# Sheet1.net
KiCad netlist of a schematic drawn in Altium Designer
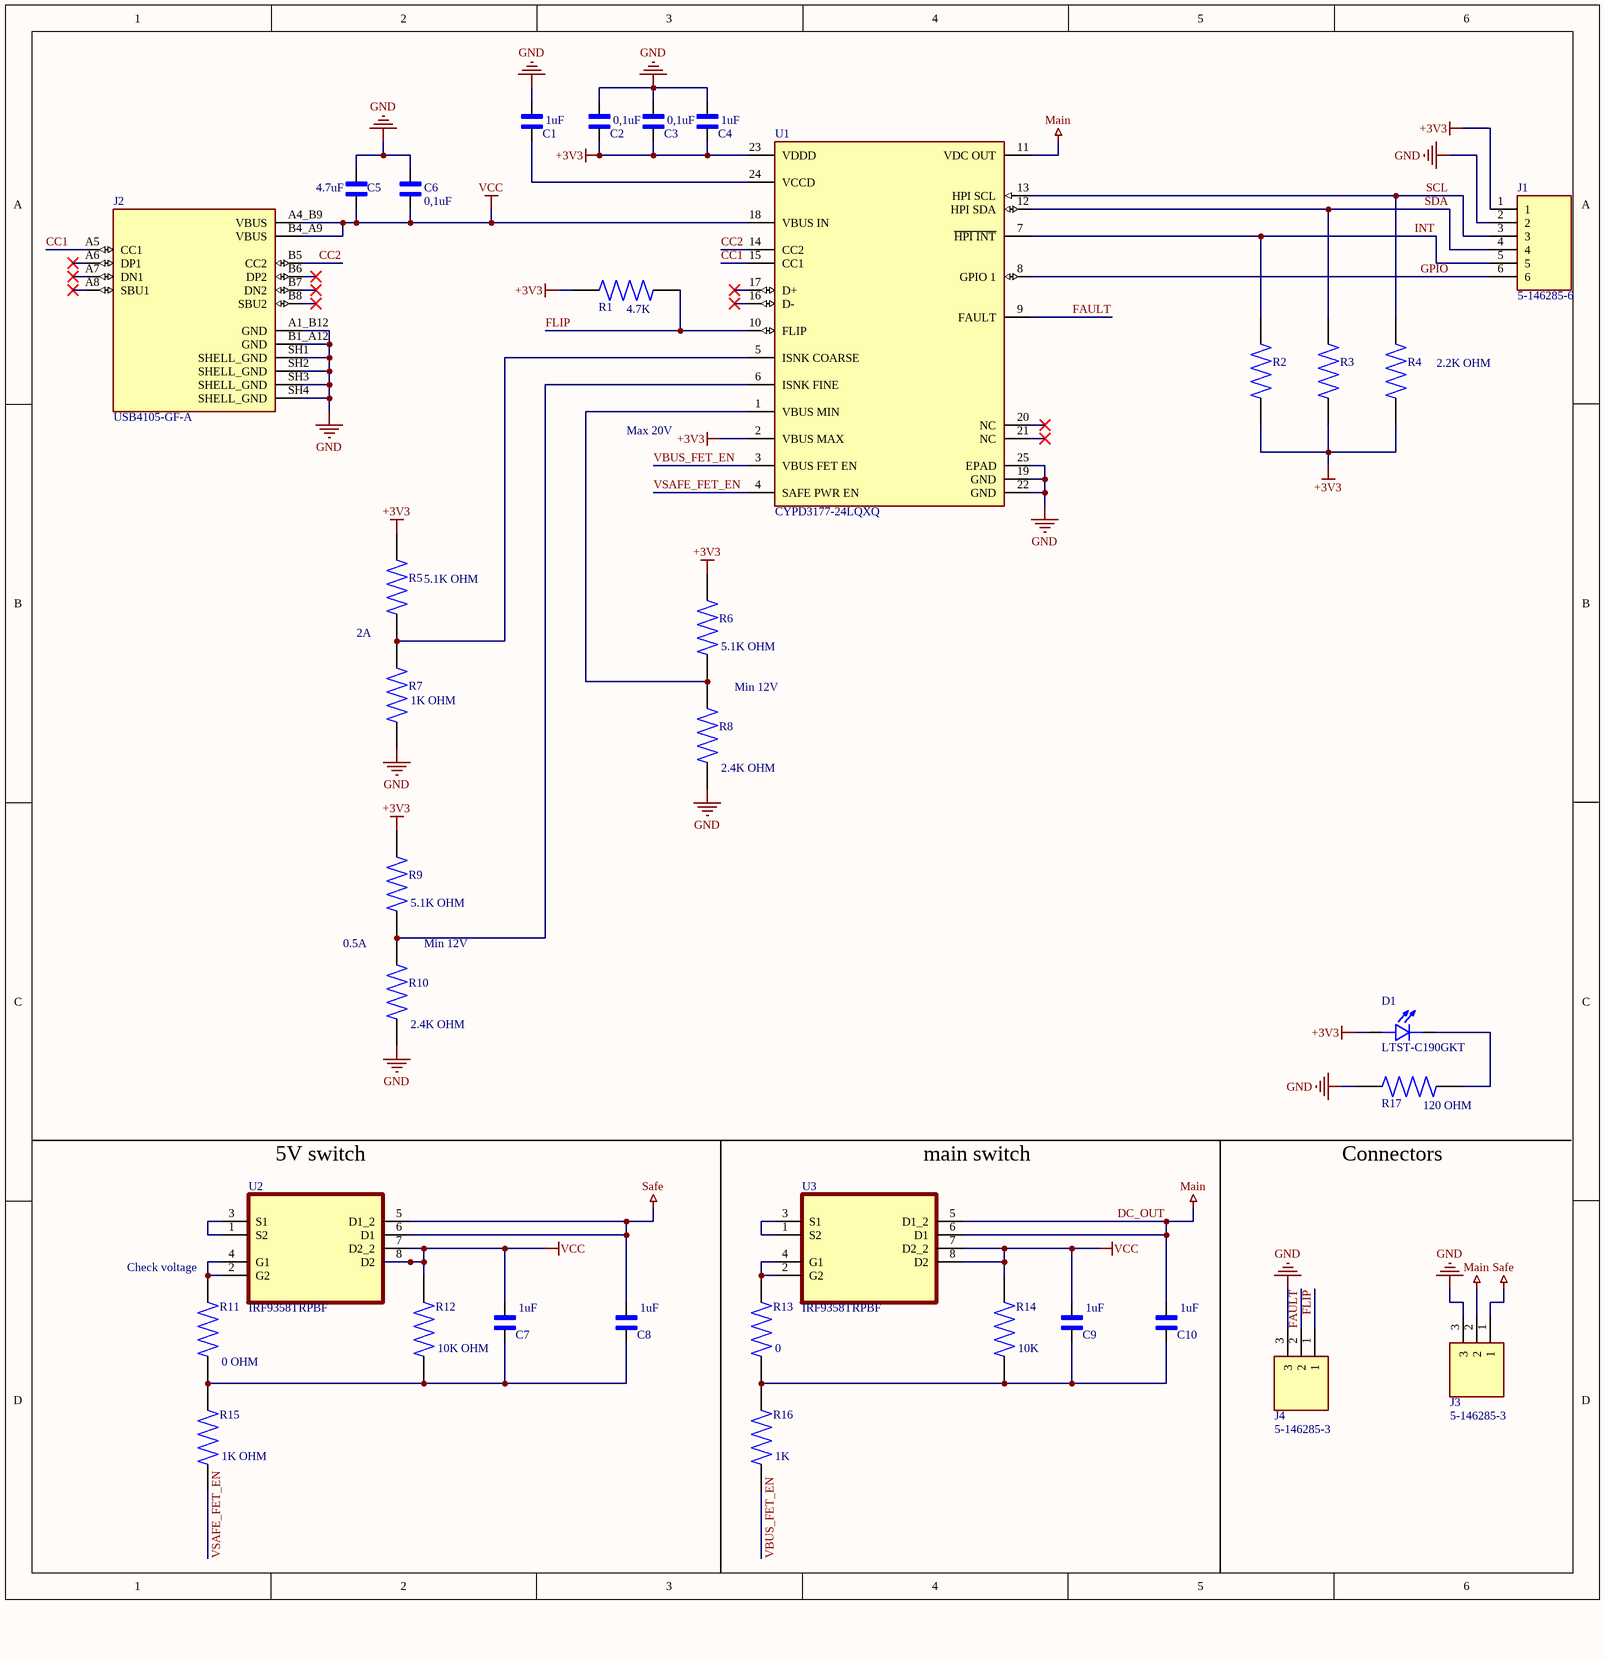
[diagram p0: Sheet1.SchDoc]

(export (version "E")
  (design (tool "Eeschema 10.0.6"))
  (components
    (comp (ref "C1")
      (value "CL10A105KB8NNNC")
      (footprint "06035C105KAT2A:CAPC1608X94N")
      (description "CAP CER 1UF 50V X5R 0603")
      (fields
        (field (name "MF") "{'manufacturer': u'KYOCERA AVX Components Corporation'}")
        (field (name "MP") "06035C105KAT2A")
      )
      (libsource (lib "*") (part "06035C105KAT2A"))
    )
    (comp (ref "C2")
      (value "CL10B104KO8NNNC")
      (footprint "06035C105KAT2A:CAPC1608X94N")
      (description "CAP CER 0.1UF 16V X7R 0603")
      (fields
        (field (name "MF") "{'manufacturer': u'KYOCERA AVX Components Corporation'}")
        (field (name "MP") "06035C105KAT2A")
      )
      (libsource (lib "*") (part "06035C105KAT2A"))
    )
    (comp (ref "C3")
      (value "CL10B104KO8NNNC")
      (footprint "06035C105KAT2A:CAPC1608X94N")
      (description "CAP CER 0.1UF 16V X7R 0603")
      (fields
        (field (name "MF") "{'manufacturer': u'KYOCERA AVX Components Corporation'}")
        (field (name "MP") "06035C105KAT2A")
      )
      (libsource (lib "*") (part "06035C105KAT2A"))
    )
    (comp (ref "C4")
      (value "CL10A105KB8NNNC")
      (footprint "06035C105KAT2A:CAPC1608X94N")
      (description "CAP CER 1UF 50V X5R 0603")
      (fields
        (field (name "MF") "{'manufacturer': u'KYOCERA AVX Components Corporation'}")
        (field (name "MP") "06035C105KAT2A")
      )
      (libsource (lib "*") (part "06035C105KAT2A"))
    )
    (comp (ref "C5")
      (value "CL21A475KBQNNNE")
      (footprint "CL21A475KBQNNNE:CAPC2012X140N")
      (description "Cap Ceramic 4.7uF 50V X5R 10% SMD 0805 85Â°C Embossed Plastic T/R")
      (fields (field (name "MF") "{'manufacturer': u'Samsung Electro-Mechanics'}"))
      (libsource (lib "*") (part "CL21A475KBQNNNE"))
    )
    (comp (ref "C6")
      (value "CL10B104KO8NNNC")
      (footprint "06035C105KAT2A:CAPC1608X94N")
      (description "CAP CER 0.1UF 16V X7R 0603")
      (fields
        (field (name "MF") "{'manufacturer': u'KYOCERA AVX Components Corporation'}")
        (field (name "MP") "06035C105KAT2A")
      )
      (libsource (lib "*") (part "06035C105KAT2A"))
    )
    (comp (ref "C7")
      (value "CL10A105KB8NNNC")
      (footprint "06035C105KAT2A:CAPC1608X94N")
      (description "CAP CER 1UF 50V X5R 0603")
      (fields
        (field (name "MF") "{'manufacturer': u'KYOCERA AVX Components Corporation'}")
        (field (name "MP") "06035C105KAT2A")
      )
      (libsource (lib "*") (part "06035C105KAT2A"))
    )
    (comp (ref "C8")
      (value "CL10A105KB8NNNC")
      (footprint "06035C105KAT2A:CAPC1608X94N")
      (description "CAP CER 1UF 50V X5R 0603")
      (fields
        (field (name "MF") "{'manufacturer': u'KYOCERA AVX Components Corporation'}")
        (field (name "MP") "06035C105KAT2A")
      )
      (libsource (lib "*") (part "06035C105KAT2A"))
    )
    (comp (ref "C9")
      (value "CL10A105KB8NNNC")
      (footprint "06035C105KAT2A:CAPC1608X94N")
      (description "CAP CER 1UF 50V X5R 0603")
      (fields
        (field (name "MF") "{'manufacturer': u'KYOCERA AVX Components Corporation'}")
        (field (name "MP") "06035C105KAT2A")
      )
      (libsource (lib "*") (part "06035C105KAT2A"))
    )
    (comp (ref "C10")
      (value "CL10A105KB8NNNC")
      (footprint "06035C105KAT2A:CAPC1608X94N")
      (description "CAP CER 1UF 50V X5R 0603")
      (fields
        (field (name "MF") "{'manufacturer': u'KYOCERA AVX Components Corporation'}")
        (field (name "MP") "06035C105KAT2A")
      )
      (libsource (lib "*") (part "06035C105KAT2A"))
    )
    (comp (ref "D1")
      (value "LTST-C190GKT")
      (footprint "LTST-C190GKT:LEDC1608X35N")
      (fields (field (name "MF") "{'manufacturer': u'Lite-On Inc.'}"))
      (libsource (lib "*") (part "LTST-C190GKT"))
    )
    (comp (ref "J1")
      (value "5-146285-6")
      (footprint "TE_5-146285-6")
      (fields (field (name "MF") "{'manufacturer': u'TE Connectivity'}"))
      (libsource (lib "5-146285-6") (part "5-146285-6"))
    )
    (comp (ref "J2")
      (value "USB4105-GF-A")
      (footprint "USB4105-GF-A:GCT_USB4105-GF-A")
      (fields (field (name "MF") "{'manufacturer': u'GCT'}"))
      (libsource (lib "USB4105-GF-A") (part "USB4105-GF-A"))
    )
    (comp (ref "J3")
      (value "5-146285-3")
      (footprint "TE_5-146285-3")
      (fields (field (name "MF") "{'manufacturer': u'TE Connectivity'}"))
      (libsource (lib "5-146285-3") (part "5-146285-3"))
    )
    (comp (ref "J4")
      (value "5-146285-3")
      (footprint "TE_5-146285-3")
      (fields (field (name "MF") "{'manufacturer': u'TE Connectivity'}"))
      (libsource (lib "5-146285-3") (part "5-146285-3"))
    )
    (comp (ref "R1")
      (value "RC0603JR-074K7L")
      (footprint "RC0603FR-0710KL:RESC1607X60N")
      (description "RES 4.7K OHM 5% 1/10W 0603")
      (fields (field (name "MF") "{'manufacturer': u'Yageo'}") (field (name "MP") "RC0603FR-0710KL"))
      (libsource (lib "*") (part "RC0603FR-0710KL"))
    )
    (comp (ref "R2")
      (value "RC0603JR-072K2L")
      (footprint "RC0603FR-0710KL:RESC1607X60N")
      (description "RES 2.2K OHM 5% 1/10W 0603")
      (fields (field (name "MF") "{'manufacturer': u'Yageo'}") (field (name "MP") "RC0603FR-0710KL"))
      (libsource (lib "*") (part "RC0603FR-0710KL"))
    )
    (comp (ref "R3")
      (value "RC0603JR-072K2L")
      (footprint "RC0603FR-0710KL:RESC1607X60N")
      (description "RES 2.2K OHM 5% 1/10W 0603")
      (fields (field (name "MF") "{'manufacturer': u'Yageo'}") (field (name "MP") "RC0603FR-0710KL"))
      (libsource (lib "*") (part "RC0603FR-0710KL"))
    )
    (comp (ref "R4")
      (value "RC0603JR-072K2L")
      (footprint "RC0603FR-0710KL:RESC1607X60N")
      (description "RES 2.2K OHM 5% 1/10W 0603")
      (fields (field (name "MF") "{'manufacturer': u'Yageo'}") (field (name "MP") "RC0603FR-0710KL"))
      (libsource (lib "*") (part "RC0603FR-0710KL"))
    )
    (comp (ref "R5")
      (value "RC0603FR-075K1L")
      (footprint "RC0603FR-0710KL:RESC1607X60N")
      (description "RES 5.1K OHM 1% 1/10W 0603")
      (fields (field (name "MF") "{'manufacturer': u'Yageo'}") (field (name "MP") "RC0603FR-0710KL"))
      (libsource (lib "*") (part "RC0603FR-0710KL"))
    )
    (comp (ref "R6")
      (value "RC0603FR-075K1L")
      (footprint "RC0603FR-0710KL:RESC1607X60N")
      (description "RES 5.1K OHM 1% 1/10W 0603")
      (fields (field (name "MF") "{'manufacturer': u'Yageo'}") (field (name "MP") "RC0603FR-0710KL"))
      (libsource (lib "*") (part "RC0603FR-0710KL"))
    )
    (comp (ref "R7")
      (value "ERJ-3EKF1001V")
      (footprint "RC0603FR-0710KL:RESC1607X60N")
      (description "RES SMD 1K OHM 1% 1/10W 0603")
      (fields (field (name "MF") "{'manufacturer': u'Yageo'}") (field (name "MP") "RC0603FR-0710KL"))
      (libsource (lib "*") (part "RC0603FR-0710KL"))
    )
    (comp (ref "R8")
      (value "RC0603FR-072K4L")
      (footprint "RC0603FR-0710KL:RESC1607X60N")
      (description "RES 2.4K OHM 1% 1/10W 0603")
      (fields (field (name "MF") "{'manufacturer': u'Yageo'}") (field (name "MP") "RC0603FR-0710KL"))
      (libsource (lib "*") (part "RC0603FR-0710KL"))
    )
    (comp (ref "R9")
      (value "RC0603FR-075K1L")
      (footprint "RC0603FR-0710KL:RESC1607X60N")
      (description "RES 5.1K OHM 1% 1/10W 0603")
      (fields (field (name "MF") "{'manufacturer': u'Yageo'}") (field (name "MP") "RC0603FR-0710KL"))
      (libsource (lib "*") (part "RC0603FR-0710KL"))
    )
    (comp (ref "R10")
      (value "RC0603FR-072K4L")
      (footprint "RC0603FR-0710KL:RESC1607X60N")
      (description "RES 2.4K OHM 1% 1/10W 0603")
      (fields (field (name "MF") "{'manufacturer': u'Yageo'}") (field (name "MP") "RC0603FR-0710KL"))
      (libsource (lib "*") (part "RC0603FR-0710KL"))
    )
    (comp (ref "R11")
      (value "ERJ-3GEY0R00V")
      (footprint "ERJ-3GEY0R00V:RES_ERJ-3GEY0R00V")
      (fields (field (name "MF") "{'manufacturer': u'Panasonic'}"))
      (libsource (lib "*") (part "ERJ-3GEY0R00V"))
    )
    (comp (ref "R12")
      (value "RC0603FR-0710KL")
      (footprint "RC0603FR-0710KL:RESC1607X60N")
      (description "RES 10K OHM 1% 1/10W 0603")
      (fields (field (name "MF") "{'manufacturer': u'Yageo'}"))
      (libsource (lib "*") (part "RC0603FR-0710KL"))
    )
    (comp (ref "R13")
      (value "ERJ-3GEY0R00V")
      (footprint "ERJ-3GEY0R00V:RES_ERJ-3GEY0R00V")
      (fields (field (name "MF") "{'manufacturer': u'Panasonic'}"))
      (libsource (lib "*") (part "ERJ-3GEY0R00V"))
    )
    (comp (ref "R14")
      (value "RC0603FR-0710KL")
      (footprint "RC0603FR-0710KL:RESC1607X60N")
      (description "RES 10K OHM 1% 1/10W 0603")
      (fields (field (name "MF") "{'manufacturer': u'Yageo'}"))
      (libsource (lib "*") (part "RC0603FR-0710KL"))
    )
    (comp (ref "R15")
      (value "ERJ-3EKF1001V")
      (footprint "ERJ-3EKF1001V:RES_ERJ3EKF1001V")
      (description "RES SMD 1K OHM 1% 1/10W 0603")
      (fields (field (name "MF") "{'manufacturer': u'Panasonic'}") (field (name "MP") "ERJ3EKF1001V"))
      (libsource (lib "*") (part "ERJ3EKF1001V"))
    )
    (comp (ref "R16")
      (value "ERJ-3EKF1001V")
      (footprint "ERJ-3EKF1001V:RES_ERJ3EKF1001V")
      (description "RES SMD 1K OHM 1% 1/10W 0603")
      (fields (field (name "MF") "{'manufacturer': u'Panasonic'}") (field (name "MP") "ERJ3EKF1001V"))
      (libsource (lib "*") (part "ERJ3EKF1001V"))
    )
    (comp (ref "R17")
      (value "RC0603FR-07120RL")
      (footprint "RC0603FR-0710KL:RESC1607X60N")
      (description "RES 120 OHM 1% 1/10W 0603")
      (fields (field (name "MF") "{'manufacturer': u'Yageo'}") (field (name "MP") "RC0603FR-0710KL"))
      (libsource (lib "*") (part "RC0603FR-0710KL"))
    )
    (comp (ref "U1")
      (value "CYPD3177-24LQXQ")
      (footprint "FP-002-16934-IPC_C")
      (description "IC USB TYPE-C PORT CONTROL 24QFN")
      (libsource (lib "Altium Content Vault") (part "568390810166e80f7277aa93be1c0e6"))
    )
    (comp (ref "U2")
      (value "IRF9358TRPBF")
      (footprint "IRF9358TRPBF:SOIC127P600X175-8N")
      (description "HEXFET Power MOSFET")
      (fields (field (name "MF") "{'manufacturer': u'Infineon'}"))
      (libsource (lib "IRF9358TRPBF") (part "IRF9358TRPBF"))
    )
    (comp (ref "U3")
      (value "IRF9358TRPBF")
      (footprint "IRF9358TRPBF:SOIC127P600X175-8N")
      (description "HEXFET Power MOSFET")
      (fields (field (name "MF") "{'manufacturer': u'Infineon'}"))
      (libsource (lib "IRF9358TRPBF") (part "IRF9358TRPBF"))
    )
  )
  (nets
    (net (code "1") (name "+3V3") (class "Default")
      (node (ref "C2") (pin "1") (pinfunction "1_1") (pintype "passive"))
      (node (ref "C3") (pin "1") (pinfunction "1_1") (pintype "passive"))
      (node (ref "C4") (pin "1") (pinfunction "1_1") (pintype "passive"))
      (node (ref "D1") (pin "A") (pinfunction "A_A") (pintype "passive"))
      (node (ref "J1") (pin "1") (pinfunction "1_1") (pintype "passive"))
      (node (ref "R1") (pin "2") (pinfunction "2_2") (pintype "passive"))
      (node (ref "R2") (pin "2") (pinfunction "2_2") (pintype "passive"))
      (node (ref "R3") (pin "2") (pinfunction "2_2") (pintype "passive"))
      (node (ref "R4") (pin "2") (pinfunction "2_2") (pintype "passive"))
      (node (ref "R5") (pin "1") (pinfunction "1_1") (pintype "passive"))
      (node (ref "R6") (pin "1") (pinfunction "1_1") (pintype "passive"))
      (node (ref "R9") (pin "1") (pinfunction "1_1") (pintype "passive"))
      (node (ref "U1") (pin "2") (pinfunction "VBUS_MAX_2") (pintype "passive"))
      (node (ref "U1") (pin "23") (pinfunction "VDDD_23") (pintype "power_in"))
    )
    (net (code "2") (name "/CC1") (class "Default")
      (node (ref "J2") (pin "A5") (pinfunction "CC1_A5") (pintype "bidirectional"))
      (node (ref "U1") (pin "15") (pinfunction "CC1_15") (pintype "passive"))
    )
    (net (code "3") (name "/CC2") (class "Default")
      (node (ref "J2") (pin "B5") (pinfunction "CC2_B5") (pintype "bidirectional"))
      (node (ref "U1") (pin "14") (pinfunction "CC2_14") (pintype "passive"))
    )
    (net (code "4") (name "/FAULT") (class "Default")
      (node (ref "J4") (pin "2") (pinfunction "2_2") (pintype "passive"))
      (node (ref "U1") (pin "9") (pinfunction "FAULT_9") (pintype "open_collector"))
    )
    (net (code "5") (name "/FLIP") (class "Default")
      (node (ref "J4") (pin "1") (pinfunction "1_1") (pintype "passive"))
      (node (ref "R1") (pin "1") (pinfunction "1_1") (pintype "passive"))
      (node (ref "U1") (pin "10") (pinfunction "FLIP_10") (pintype "bidirectional"))
    )
    (net (code "6") (name "/GPIO") (class "Default")
      (node (ref "J1") (pin "6") (pinfunction "6_6") (pintype "passive"))
      (node (ref "U1") (pin "8") (pinfunction "GPIO_1_8") (pintype "bidirectional"))
    )
    (net (code "7") (name "/INT") (class "Default")
      (node (ref "J1") (pin "5") (pinfunction "5_5") (pintype "passive"))
      (node (ref "R2") (pin "1") (pinfunction "1_1") (pintype "passive"))
      (node (ref "U1") (pin "7") (pinfunction "~{HPI_INT}_7") (pintype "passive"))
    )
    (net (code "8") (name "/SCL") (class "Default")
      (node (ref "J1") (pin "3") (pinfunction "3_3") (pintype "passive"))
      (node (ref "R4") (pin "1") (pinfunction "1_1") (pintype "passive"))
      (node (ref "U1") (pin "13") (pinfunction "HPI_SCL_13") (pintype "input"))
    )
    (net (code "9") (name "/SDA") (class "Default")
      (node (ref "J1") (pin "4") (pinfunction "4_4") (pintype "passive"))
      (node (ref "R3") (pin "1") (pinfunction "1_1") (pintype "passive"))
      (node (ref "U1") (pin "12") (pinfunction "HPI_SDA_12") (pintype "bidirectional"))
    )
    (net (code "10") (name "/VBUS_FET_EN") (class "Default")
      (node (ref "R16") (pin "1") (pinfunction "1_1") (pintype "passive"))
      (node (ref "U1") (pin "3") (pinfunction "VBUS_FET_EN_3") (pintype "passive"))
    )
    (net (code "11") (name "/VSAFE_FET_EN") (class "Default")
      (node (ref "R15") (pin "1") (pinfunction "1_1") (pintype "passive"))
      (node (ref "U1") (pin "4") (pinfunction "SAFE_PWR_EN_4") (pintype "passive"))
    )
    (net (code "12") (name "GND") (class "Default")
      (node (ref "C1") (pin "2") (pinfunction "2_2") (pintype "passive"))
      (node (ref "C2") (pin "2") (pinfunction "2_2") (pintype "passive"))
      (node (ref "C3") (pin "2") (pinfunction "2_2") (pintype "passive"))
      (node (ref "C4") (pin "2") (pinfunction "2_2") (pintype "passive"))
      (node (ref "C5") (pin "1") (pinfunction "1_1") (pintype "passive"))
      (node (ref "C6") (pin "2") (pinfunction "2_2") (pintype "passive"))
      (node (ref "J1") (pin "2") (pinfunction "2_2") (pintype "passive"))
      (node (ref "J2") (pin "A1_B12") (pinfunction "GND_A1_B12") (pintype "power_in"))
      (node (ref "J2") (pin "B1_A12") (pinfunction "GND_B1_A12") (pintype "power_in"))
      (node (ref "J2") (pin "SH1") (pinfunction "SHELL_GND_SH1") (pintype "power_in"))
      (node (ref "J2") (pin "SH2") (pinfunction "SHELL_GND_SH2") (pintype "power_in"))
      (node (ref "J2") (pin "SH3") (pinfunction "SHELL_GND_SH3") (pintype "power_in"))
      (node (ref "J2") (pin "SH4") (pinfunction "SHELL_GND_SH4") (pintype "power_in"))
      (node (ref "J3") (pin "3") (pinfunction "3_3") (pintype "passive"))
      (node (ref "J4") (pin "3") (pinfunction "3_3") (pintype "passive"))
      (node (ref "R10") (pin "2") (pinfunction "2_2") (pintype "passive"))
      (node (ref "R17") (pin "1") (pinfunction "1_1") (pintype "passive"))
      (node (ref "R7") (pin "2") (pinfunction "2_2") (pintype "passive"))
      (node (ref "R8") (pin "2") (pinfunction "2_2") (pintype "passive"))
      (node (ref "U1") (pin "19") (pinfunction "GND_19") (pintype "power_in"))
      (node (ref "U1") (pin "22") (pinfunction "GND_22") (pintype "power_in"))
      (node (ref "U1") (pin "25") (pinfunction "EPAD_25") (pintype "power_in"))
    )
    (net (code "13") (name "Main") (class "Default")
      (node (ref "C10") (pin "2") (pinfunction "2_2") (pintype "passive"))
      (node (ref "J3") (pin "2") (pinfunction "2_2") (pintype "passive"))
      (node (ref "U1") (pin "11") (pinfunction "VDC_OUT_11") (pintype "passive"))
      (node (ref "U3") (pin "5") (pinfunction "D1_2_5") (pintype "passive"))
      (node (ref "U3") (pin "6") (pinfunction "D1_6") (pintype "passive"))
    )
    (net (code "14") (name "Net-(C7-Pad1)") (class "Default")
      (node (ref "C7") (pin "1") (pinfunction "1_1") (pintype "passive"))
      (node (ref "C8") (pin "1") (pinfunction "1_1") (pintype "passive"))
      (node (ref "R11") (pin "1") (pinfunction "1_1") (pintype "passive"))
      (node (ref "R12") (pin "1") (pinfunction "1_1") (pintype "passive"))
      (node (ref "R15") (pin "2") (pinfunction "2_2") (pintype "passive"))
    )
    (net (code "15") (name "Net-(C10-Pad1)") (class "Default")
      (node (ref "C10") (pin "1") (pinfunction "1_1") (pintype "passive"))
      (node (ref "C9") (pin "1") (pinfunction "1_1") (pintype "passive"))
      (node (ref "R13") (pin "1") (pinfunction "1_1") (pintype "passive"))
      (node (ref "R14") (pin "1") (pinfunction "1_1") (pintype "passive"))
      (node (ref "R16") (pin "2") (pinfunction "2_2") (pintype "passive"))
    )
    (net (code "16") (name "Net-(D1-PadC)") (class "Default")
      (node (ref "D1") (pin "C") (pinfunction "C_C") (pintype "passive"))
      (node (ref "R17") (pin "2") (pinfunction "2_2") (pintype "passive"))
    )
    (net (code "17") (name "Net-(U1-ISNK_COARSE)") (class "Default")
      (node (ref "R5") (pin "2") (pinfunction "2_2") (pintype "passive"))
      (node (ref "R7") (pin "1") (pinfunction "1_1") (pintype "passive"))
      (node (ref "U1") (pin "5") (pinfunction "ISNK_COARSE_5") (pintype "passive"))
    )
    (net (code "18") (name "Net-(U1-ISNK_FINE)") (class "Default")
      (node (ref "R10") (pin "1") (pinfunction "1_1") (pintype "passive"))
      (node (ref "R9") (pin "2") (pinfunction "2_2") (pintype "passive"))
      (node (ref "U1") (pin "6") (pinfunction "ISNK_FINE_6") (pintype "passive"))
    )
    (net (code "19") (name "Net-(U1-VBUS_MIN)") (class "Default")
      (node (ref "R6") (pin "2") (pinfunction "2_2") (pintype "passive"))
      (node (ref "R8") (pin "1") (pinfunction "1_1") (pintype "passive"))
      (node (ref "U1") (pin "1") (pinfunction "VBUS_MIN_1") (pintype "passive"))
    )
    (net (code "20") (name "Net-(U1-VCCD)") (class "Default")
      (node (ref "C1") (pin "1") (pinfunction "1_1") (pintype "passive"))
      (node (ref "U1") (pin "24") (pinfunction "VCCD_24") (pintype "power_in"))
    )
    (net (code "21") (name "Net-(U2-G1)") (class "Default")
      (node (ref "R11") (pin "2") (pinfunction "2_2") (pintype "passive"))
      (node (ref "U2") (pin "2") (pinfunction "G2_2") (pintype "passive"))
      (node (ref "U2") (pin "4") (pinfunction "G1_4") (pintype "passive"))
    )
    (net (code "22") (name "Net-(U2-S1)") (class "Default")
      (node (ref "U2") (pin "1") (pinfunction "S2_1") (pintype "passive"))
      (node (ref "U2") (pin "3") (pinfunction "S1_3") (pintype "passive"))
    )
    (net (code "23") (name "Net-(U3-G1)") (class "Default")
      (node (ref "R13") (pin "2") (pinfunction "2_2") (pintype "passive"))
      (node (ref "U3") (pin "2") (pinfunction "G2_2") (pintype "passive"))
      (node (ref "U3") (pin "4") (pinfunction "G1_4") (pintype "passive"))
    )
    (net (code "24") (name "Net-(U3-S1)") (class "Default")
      (node (ref "U3") (pin "1") (pinfunction "S2_1") (pintype "passive"))
      (node (ref "U3") (pin "3") (pinfunction "S1_3") (pintype "passive"))
    )
    (net (code "25") (name "Safe") (class "Default")
      (node (ref "C8") (pin "2") (pinfunction "2_2") (pintype "passive"))
      (node (ref "J3") (pin "1") (pinfunction "1_1") (pintype "passive"))
      (node (ref "U2") (pin "5") (pinfunction "D1_2_5") (pintype "passive"))
      (node (ref "U2") (pin "6") (pinfunction "D1_6") (pintype "passive"))
    )
    (net (code "26") (name "VCC") (class "Default")
      (node (ref "C5") (pin "2") (pinfunction "2_2") (pintype "passive"))
      (node (ref "C6") (pin "1") (pinfunction "1_1") (pintype "passive"))
      (node (ref "C7") (pin "2") (pinfunction "2_2") (pintype "passive"))
      (node (ref "C9") (pin "2") (pinfunction "2_2") (pintype "passive"))
      (node (ref "J2") (pin "A4_B9") (pinfunction "VBUS_A4_B9") (pintype "power_in"))
      (node (ref "J2") (pin "B4_A9") (pinfunction "VBUS_B4_A9") (pintype "power_in"))
      (node (ref "R12") (pin "2") (pinfunction "2_2") (pintype "passive"))
      (node (ref "R14") (pin "2") (pinfunction "2_2") (pintype "passive"))
      (node (ref "U1") (pin "18") (pinfunction "VBUS_IN_18") (pintype "power_in"))
      (node (ref "U2") (pin "7") (pinfunction "D2_2_7") (pintype "passive"))
      (node (ref "U2") (pin "8") (pinfunction "D2_8") (pintype "passive"))
      (node (ref "U3") (pin "7") (pinfunction "D2_2_7") (pintype "passive"))
      (node (ref "U3") (pin "8") (pinfunction "D2_8") (pintype "passive"))
    )
    (net (code "27") (name "unconnected-(J2-DN1-PadA7)") (class "Default")
      (node (ref "J2") (pin "A7") (pinfunction "DN1_A7") (pintype "bidirectional+no_connect"))
    )
    (net (code "28") (name "unconnected-(J2-DN2-PadB7)") (class "Default")
      (node (ref "J2") (pin "B7") (pinfunction "DN2_B7") (pintype "bidirectional+no_connect"))
    )
    (net (code "29") (name "unconnected-(J2-DP1-PadA6)") (class "Default")
      (node (ref "J2") (pin "A6") (pinfunction "DP1_A6") (pintype "bidirectional+no_connect"))
    )
    (net (code "30") (name "unconnected-(J2-DP2-PadB6)") (class "Default")
      (node (ref "J2") (pin "B6") (pinfunction "DP2_B6") (pintype "bidirectional+no_connect"))
    )
    (net (code "31") (name "unconnected-(J2-SBU1-PadA8)") (class "Default")
      (node (ref "J2") (pin "A8") (pinfunction "SBU1_A8") (pintype "bidirectional+no_connect"))
    )
    (net (code "32") (name "unconnected-(J2-SBU2-PadB8)") (class "Default")
      (node (ref "J2") (pin "B8") (pinfunction "SBU2_B8") (pintype "bidirectional+no_connect"))
    )
    (net (code "33") (name "unconnected-(U1-D+-Pad17)") (class "Default")
      (node (ref "U1") (pin "17") (pinfunction "D+_17") (pintype "bidirectional+no_connect"))
    )
    (net (code "34") (name "unconnected-(U1-D--Pad16)") (class "Default")
      (node (ref "U1") (pin "16") (pinfunction "D-_16") (pintype "bidirectional+no_connect"))
    )
    (net (code "35") (name "unconnected-(U1-NC-Pad20)") (class "Default")
      (node (ref "U1") (pin "20") (pinfunction "NC_20") (pintype "passive+no_connect"))
    )
    (net (code "36") (name "unconnected-(U1-NC-Pad21)") (class "Default")
      (node (ref "U1") (pin "21") (pinfunction "NC_21") (pintype "passive+no_connect"))
    )
  )
)
